# StewartPlatform.net
KiCad netlist of a schematic drawn in EAGLE
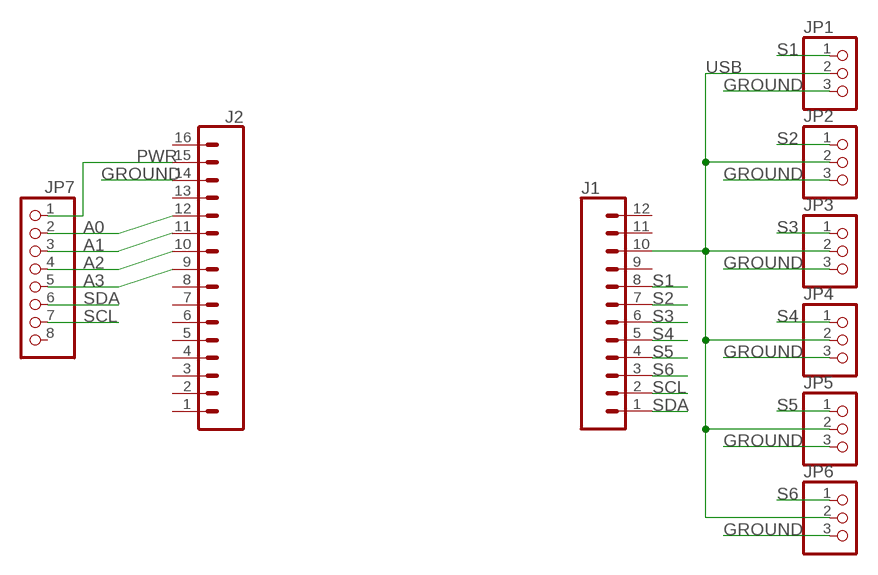
[diagram p0: schematic, sheet 1]

(export (version "E")
  (design (tool "Eeschema 10.0.6"))
  (components
    (comp (ref "J1")
      (value "SPARKFUN-CONNECTORS_CONN_12")
      (footprint "eagle-import:SPARKFUN-CONNECTORS_1X12")
      (libsource (lib "eagle-import") (part "SPARKFUN-CONNECTORS_CONN_12"))
    )
    (comp (ref "J2")
      (value "SPARKFUN-CONNECTORS_CONN_16")
      (footprint "eagle-import:SPARKFUN-CONNECTORS_1X16")
      (libsource (lib "eagle-import") (part "SPARKFUN-CONNECTORS_CONN_16"))
    )
    (comp (ref "JP1")
      (value "RARNDT-MISCELANEOUS_PINHD-1X3")
      (footprint "eagle-import:RARNDT-MISCELANEOUS_1X03")
      (libsource (lib "eagle-import") (part "RARNDT-MISCELANEOUS_PINHD-1X3"))
    )
    (comp (ref "JP2")
      (value "RARNDT-MISCELANEOUS_PINHD-1X3")
      (footprint "eagle-import:RARNDT-MISCELANEOUS_1X03")
      (libsource (lib "eagle-import") (part "RARNDT-MISCELANEOUS_PINHD-1X3"))
    )
    (comp (ref "JP3")
      (value "RARNDT-MISCELANEOUS_PINHD-1X3")
      (footprint "eagle-import:RARNDT-MISCELANEOUS_1X03")
      (libsource (lib "eagle-import") (part "RARNDT-MISCELANEOUS_PINHD-1X3"))
    )
    (comp (ref "JP4")
      (value "RARNDT-MISCELANEOUS_PINHD-1X3")
      (footprint "eagle-import:RARNDT-MISCELANEOUS_1X03")
      (libsource (lib "eagle-import") (part "RARNDT-MISCELANEOUS_PINHD-1X3"))
    )
    (comp (ref "JP5")
      (value "RARNDT-MISCELANEOUS_PINHD-1X3")
      (footprint "eagle-import:RARNDT-MISCELANEOUS_1X03")
      (libsource (lib "eagle-import") (part "RARNDT-MISCELANEOUS_PINHD-1X3"))
    )
    (comp (ref "JP6")
      (value "RARNDT-MISCELANEOUS_PINHD-1X3")
      (footprint "eagle-import:RARNDT-MISCELANEOUS_1X03")
      (libsource (lib "eagle-import") (part "RARNDT-MISCELANEOUS_PINHD-1X3"))
    )
    (comp (ref "JP7")
      (value "PINHD-1X8")
      (footprint "eagle-import:1X08")
      (libsource (lib "eagle-import") (part "PINHD-1X8"))
    )
  )
  (nets
    (net (code "1") (name "/A0") (class "Default")
      (node (ref "J2") (pin "12") (pinfunction "12_12") (pintype "passive"))
      (node (ref "JP7") (pin "2") (pinfunction "2_2") (pintype "passive"))
    )
    (net (code "2") (name "/A1") (class "Default")
      (node (ref "J2") (pin "11") (pinfunction "11_11") (pintype "passive"))
      (node (ref "JP7") (pin "3") (pinfunction "3_3") (pintype "passive"))
    )
    (net (code "3") (name "/A2") (class "Default")
      (node (ref "J2") (pin "10") (pinfunction "10_10") (pintype "passive"))
      (node (ref "JP7") (pin "4") (pinfunction "4_4") (pintype "passive"))
    )
    (net (code "4") (name "/A3") (class "Default")
      (node (ref "J2") (pin "9") (pinfunction "9_9") (pintype "passive"))
      (node (ref "JP7") (pin "5") (pinfunction "5_5") (pintype "passive"))
    )
    (net (code "5") (name "/GROUND") (class "Default")
      (node (ref "J2") (pin "14") (pinfunction "14_14") (pintype "passive"))
      (node (ref "JP1") (pin "3") (pinfunction "3_3") (pintype "passive"))
      (node (ref "JP2") (pin "3") (pinfunction "3_3") (pintype "passive"))
      (node (ref "JP3") (pin "3") (pinfunction "3_3") (pintype "passive"))
      (node (ref "JP4") (pin "3") (pinfunction "3_3") (pintype "passive"))
      (node (ref "JP5") (pin "3") (pinfunction "3_3") (pintype "passive"))
      (node (ref "JP6") (pin "3") (pinfunction "3_3") (pintype "passive"))
    )
    (net (code "6") (name "/PWR") (class "Default")
      (node (ref "J2") (pin "15") (pinfunction "15_15") (pintype "passive"))
      (node (ref "JP7") (pin "1") (pinfunction "1_1") (pintype "passive"))
    )
    (net (code "7") (name "/S1") (class "Default")
      (node (ref "J1") (pin "8") (pinfunction "8_8") (pintype "passive"))
      (node (ref "JP1") (pin "1") (pinfunction "1_1") (pintype "passive"))
    )
    (net (code "8") (name "/S2") (class "Default")
      (node (ref "J1") (pin "7") (pinfunction "7_7") (pintype "passive"))
      (node (ref "JP2") (pin "1") (pinfunction "1_1") (pintype "passive"))
    )
    (net (code "9") (name "/S3") (class "Default")
      (node (ref "J1") (pin "6") (pinfunction "6_6") (pintype "passive"))
      (node (ref "JP3") (pin "1") (pinfunction "1_1") (pintype "passive"))
    )
    (net (code "10") (name "/S4") (class "Default")
      (node (ref "J1") (pin "5") (pinfunction "5_5") (pintype "passive"))
      (node (ref "JP4") (pin "1") (pinfunction "1_1") (pintype "passive"))
    )
    (net (code "11") (name "/S5") (class "Default")
      (node (ref "J1") (pin "4") (pinfunction "4_4") (pintype "passive"))
      (node (ref "JP5") (pin "1") (pinfunction "1_1") (pintype "passive"))
    )
    (net (code "12") (name "/S6") (class "Default")
      (node (ref "J1") (pin "3") (pinfunction "3_3") (pintype "passive"))
      (node (ref "JP6") (pin "1") (pinfunction "1_1") (pintype "passive"))
    )
    (net (code "13") (name "/SCL") (class "Default")
      (node (ref "J1") (pin "2") (pinfunction "2_2") (pintype "passive"))
      (node (ref "JP7") (pin "7") (pinfunction "7_7") (pintype "passive"))
    )
    (net (code "14") (name "/SDA") (class "Default")
      (node (ref "J1") (pin "1") (pinfunction "1_1") (pintype "passive"))
      (node (ref "JP7") (pin "6") (pinfunction "6_6") (pintype "passive"))
    )
    (net (code "15") (name "/USB") (class "Default")
      (node (ref "J1") (pin "10") (pinfunction "10_10") (pintype "passive"))
      (node (ref "JP1") (pin "2") (pinfunction "2_2") (pintype "passive"))
      (node (ref "JP2") (pin "2") (pinfunction "2_2") (pintype "passive"))
      (node (ref "JP3") (pin "2") (pinfunction "2_2") (pintype "passive"))
      (node (ref "JP4") (pin "2") (pinfunction "2_2") (pintype "passive"))
      (node (ref "JP5") (pin "2") (pinfunction "2_2") (pintype "passive"))
      (node (ref "JP6") (pin "2") (pinfunction "2_2") (pintype "passive"))
    )
    (net (code "16") (name "unconnected-(J1-Pad9)") (class "Default")
      (node (ref "J1") (pin "9") (pinfunction "9_9") (pintype "passive"))
    )
    (net (code "17") (name "unconnected-(J1-Pad11)") (class "Default")
      (node (ref "J1") (pin "11") (pinfunction "11_11") (pintype "passive"))
    )
    (net (code "18") (name "unconnected-(J1-Pad12)") (class "Default")
      (node (ref "J1") (pin "12") (pinfunction "12_12") (pintype "passive"))
    )
    (net (code "19") (name "unconnected-(J2-Pad1)") (class "Default")
      (node (ref "J2") (pin "1") (pinfunction "1_1") (pintype "passive"))
    )
    (net (code "20") (name "unconnected-(J2-Pad2)") (class "Default")
      (node (ref "J2") (pin "2") (pinfunction "2_2") (pintype "passive"))
    )
    (net (code "21") (name "unconnected-(J2-Pad3)") (class "Default")
      (node (ref "J2") (pin "3") (pinfunction "3_3") (pintype "passive"))
    )
    (net (code "22") (name "unconnected-(J2-Pad4)") (class "Default")
      (node (ref "J2") (pin "4") (pinfunction "4_4") (pintype "passive"))
    )
    (net (code "23") (name "unconnected-(J2-Pad5)") (class "Default")
      (node (ref "J2") (pin "5") (pinfunction "5_5") (pintype "passive"))
    )
    (net (code "24") (name "unconnected-(J2-Pad6)") (class "Default")
      (node (ref "J2") (pin "6") (pinfunction "6_6") (pintype "passive"))
    )
    (net (code "25") (name "unconnected-(J2-Pad7)") (class "Default")
      (node (ref "J2") (pin "7") (pinfunction "7_7") (pintype "passive"))
    )
    (net (code "26") (name "unconnected-(J2-Pad8)") (class "Default")
      (node (ref "J2") (pin "8") (pinfunction "8_8") (pintype "passive"))
    )
    (net (code "27") (name "unconnected-(J2-Pad13)") (class "Default")
      (node (ref "J2") (pin "13") (pinfunction "13_13") (pintype "passive"))
    )
    (net (code "28") (name "unconnected-(J2-Pad16)") (class "Default")
      (node (ref "J2") (pin "16") (pinfunction "16_16") (pintype "passive"))
    )
    (net (code "29") (name "unconnected-(JP7-Pad8)") (class "Default")
      (node (ref "JP7") (pin "8") (pinfunction "8_8") (pintype "passive"))
    )
  )
)
